# predajnik.net
KiCad netlist of a schematic drawn in EAGLE
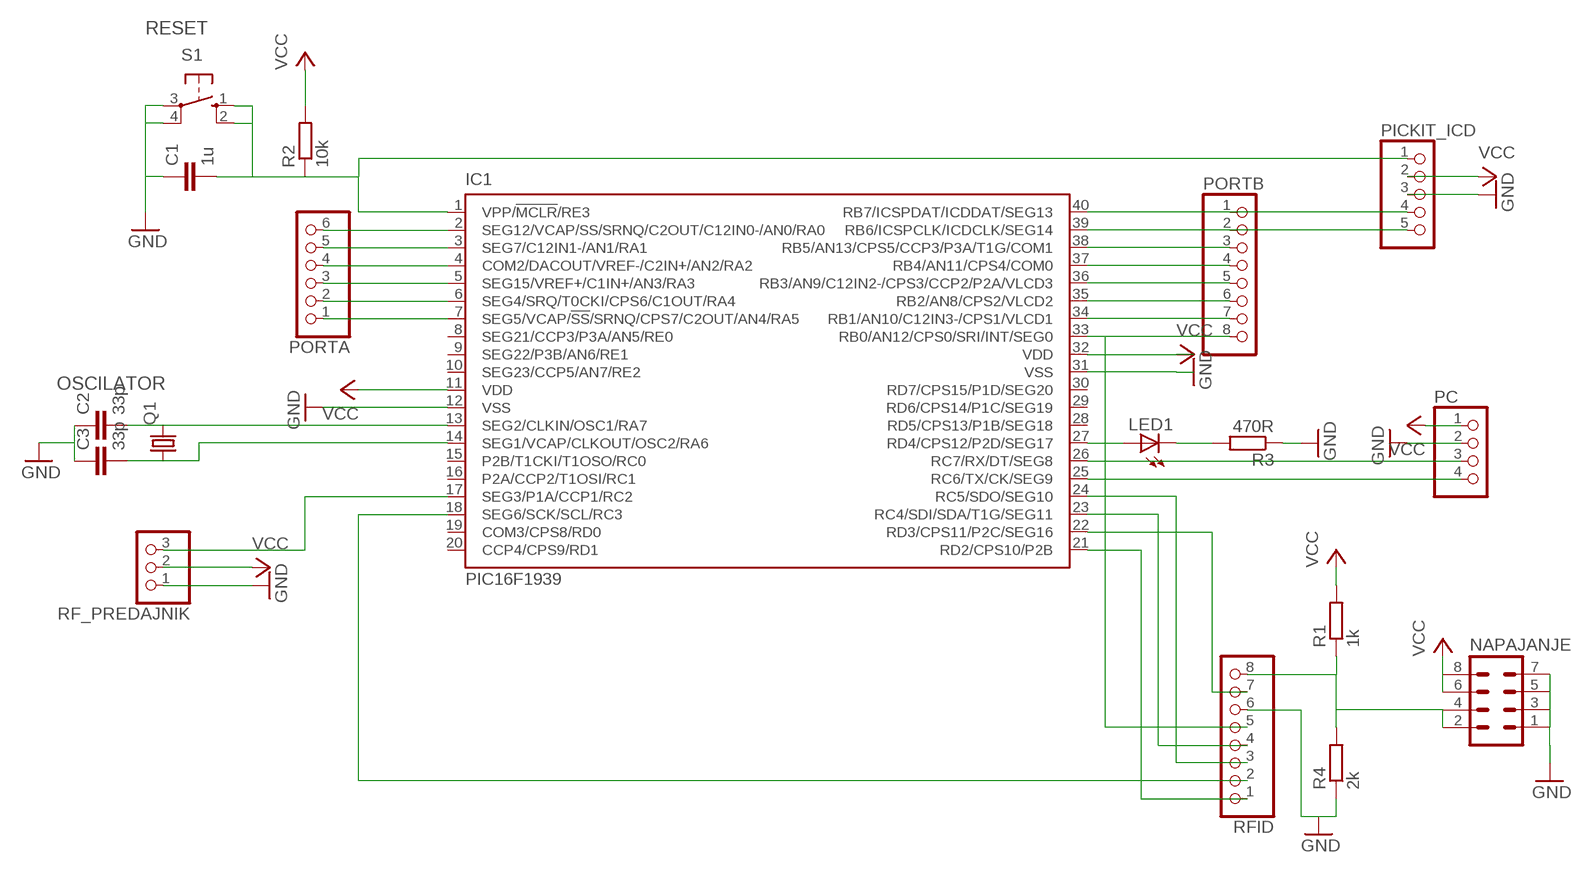
[diagram p0: schematic, sheet 1]

(export (version "E")
  (design (tool "Eeschema 10.0.6"))
  (components
    (comp (ref "C1")
      (value "1u")
      (footprint "eagle-import:C050-024X044")
      (libsource (lib "eagle-import") (part "C-EU050-024X044"))
    )
    (comp (ref "C2")
      (value "33p")
      (footprint "eagle-import:C025-024X044")
      (libsource (lib "eagle-import") (part "C-EU025-024X044"))
    )
    (comp (ref "C3")
      (value "33p")
      (footprint "eagle-import:C025-024X044")
      (libsource (lib "eagle-import") (part "C-EU025-024X044"))
    )
    (comp (ref "IC1")
      (value "PIC16F1939")
      (footprint "eagle-import:DIL40")
      (libsource (lib "eagle-import") (part "PIC16F193?"))
    )
    (comp (ref "LED1")
      (value "LED5MM")
      (footprint "eagle-import:LED5MM")
      (libsource (lib "eagle-import") (part "LED5MM"))
    )
    (comp (ref "NAPAJANJE")
      (value "MA04-2")
      (footprint "eagle-import:MA04-2")
      (libsource (lib "eagle-import") (part "MA04-2"))
    )
    (comp (ref "PC")
      (value "PINHD-1X4")
      (footprint "eagle-import:1X04")
      (libsource (lib "eagle-import") (part "PINHD-1X4"))
    )
    (comp (ref "PICKIT_ICD")
      (value "PINHD-1X5")
      (footprint "eagle-import:1X05")
      (libsource (lib "eagle-import") (part "PINHD-1X5"))
    )
    (comp (ref "PORTA")
      (value "PINHD-1X6")
      (footprint "eagle-import:1X06")
      (libsource (lib "eagle-import") (part "PINHD-1X6"))
    )
    (comp (ref "PORTB")
      (value "PINHD-1X8")
      (footprint "eagle-import:1X08")
      (libsource (lib "eagle-import") (part "PINHD-1X8"))
    )
    (comp (ref "Q1")
      (value "CRYSTALHC49S")
      (footprint "eagle-import:HC49_S")
      (libsource (lib "eagle-import") (part "CRYSTALHC49S"))
    )
    (comp (ref "R1")
      (value "1k")
      (footprint "eagle-import:0207_10")
      (libsource (lib "eagle-import") (part "R-EU_0207/10"))
    )
    (comp (ref "R2")
      (value "10k")
      (footprint "eagle-import:0207_10")
      (libsource (lib "eagle-import") (part "R-EU_0207/10"))
    )
    (comp (ref "R3")
      (value "470R")
      (footprint "eagle-import:0207_10")
      (libsource (lib "eagle-import") (part "R-EU_0207/10"))
    )
    (comp (ref "R4")
      (value "2k")
      (footprint "eagle-import:0207_10")
      (libsource (lib "eagle-import") (part "R-EU_0207/10"))
    )
    (comp (ref "RFID")
      (value "PINHD-1X8")
      (footprint "eagle-import:1X08")
      (libsource (lib "eagle-import") (part "PINHD-1X8"))
    )
    (comp (ref "RF_PREDAJNIK")
      (value "PINHD-1X3")
      (footprint "eagle-import:1X03")
      (libsource (lib "eagle-import") (part "PINHD-1X3"))
    )
    (comp (ref "S1")
      (value "10-XX")
      (footprint "eagle-import:B3F-10XX")
      (fields (field (name "MPN") "B3F-1000"))
      (libsource (lib "eagle-import") (part "10-XX"))
    )
  )
  (nets
    (net (code "1") (name "GND") (class "Default")
      (node (ref "C1") (pin "1") (pinfunction "1_1") (pintype "passive"))
      (node (ref "C2") (pin "1") (pinfunction "1_1") (pintype "passive"))
      (node (ref "C3") (pin "1") (pinfunction "1_1") (pintype "passive"))
      (node (ref "IC1") (pin "12") (pinfunction "VSS_12") (pintype "power_in"))
      (node (ref "IC1") (pin "31") (pinfunction "VSS_31") (pintype "power_in"))
      (node (ref "NAPAJANJE") (pin "1") (pinfunction "1_1") (pintype "passive"))
      (node (ref "NAPAJANJE") (pin "3") (pinfunction "3_3") (pintype "passive"))
      (node (ref "NAPAJANJE") (pin "5") (pinfunction "5_5") (pintype "passive"))
      (node (ref "NAPAJANJE") (pin "7") (pinfunction "7_7") (pintype "passive"))
      (node (ref "PC") (pin "2") (pinfunction "2_2") (pintype "passive"))
      (node (ref "PICKIT_ICD") (pin "3") (pinfunction "3_3") (pintype "passive"))
      (node (ref "R3") (pin "1") (pinfunction "1_1") (pintype "passive"))
      (node (ref "R4") (pin "1") (pinfunction "1_1") (pintype "passive"))
      (node (ref "RFID") (pin "6") (pinfunction "6_6") (pintype "passive"))
      (node (ref "RF_PREDAJNIK") (pin "1") (pinfunction "1_1") (pintype "passive"))
      (node (ref "S1") (pin "3") (pinfunction "P_3") (pintype "passive"))
      (node (ref "S1") (pin "4") (pinfunction "P1_4") (pintype "passive"))
    )
    (net (code "2") (name "Net-(IC1-COM2{slash}DACOUT{slash}VREF-{slash}C2IN+{slash}AN2{slash}RA2)") (class "Default")
      (node (ref "IC1") (pin "4") (pinfunction "COM2/DACOUT/VREF-/C2IN+/AN2/RA2_4") (pintype "bidirectional"))
      (node (ref "PORTA") (pin "4") (pinfunction "4_4") (pintype "passive"))
    )
    (net (code "3") (name "Net-(IC1-RB0{slash}AN12{slash}CPS0{slash}SRI{slash}INT{slash}SEG0)") (class "Default")
      (node (ref "IC1") (pin "33") (pinfunction "RB0/AN12/CPS0/SRI/INT/SEG0_33") (pintype "bidirectional"))
      (node (ref "PORTB") (pin "8") (pinfunction "8_8") (pintype "passive"))
      (node (ref "RFID") (pin "5") (pinfunction "5_5") (pintype "passive"))
    )
    (net (code "4") (name "Net-(IC1-RB1{slash}AN10{slash}C12IN3-{slash}CPS1{slash}VLCD1)") (class "Default")
      (node (ref "IC1") (pin "34") (pinfunction "RB1/AN10/C12IN3-/CPS1/VLCD1_34") (pintype "bidirectional"))
      (node (ref "PORTB") (pin "7") (pinfunction "7_7") (pintype "passive"))
    )
    (net (code "5") (name "Net-(IC1-RB2{slash}AN8{slash}CPS2{slash}VLCD2)") (class "Default")
      (node (ref "IC1") (pin "35") (pinfunction "RB2/AN8/CPS2/VLCD2_35") (pintype "bidirectional"))
      (node (ref "PORTB") (pin "6") (pinfunction "6_6") (pintype "passive"))
    )
    (net (code "6") (name "Net-(IC1-RB3{slash}AN9{slash}C12IN2-{slash}CPS3{slash}CCP2{slash}P2A{slash}VLCD3)") (class "Default")
      (node (ref "IC1") (pin "36") (pinfunction "RB3/AN9/C12IN2-/CPS3/CCP2/P2A/VLCD3_36") (pintype "bidirectional"))
      (node (ref "PORTB") (pin "5") (pinfunction "5_5") (pintype "passive"))
    )
    (net (code "7") (name "Net-(IC1-RB4{slash}AN11{slash}CPS4{slash}COM0)") (class "Default")
      (node (ref "IC1") (pin "37") (pinfunction "RB4/AN11/CPS4/COM0_37") (pintype "bidirectional"))
      (node (ref "PORTB") (pin "4") (pinfunction "4_4") (pintype "passive"))
    )
    (net (code "8") (name "Net-(IC1-RB5{slash}AN13{slash}CPS5{slash}CCP3{slash}P3A{slash}T1G{slash}COM1)") (class "Default")
      (node (ref "IC1") (pin "38") (pinfunction "RB5/AN13/CPS5/CCP3/P3A/T1G/COM1_38") (pintype "bidirectional"))
      (node (ref "PORTB") (pin "3") (pinfunction "3_3") (pintype "passive"))
    )
    (net (code "9") (name "Net-(IC1-RB6{slash}ICSPCLK{slash}ICDCLK{slash}SEG14)") (class "Default")
      (node (ref "IC1") (pin "39") (pinfunction "RB6/ICSPCLK/ICDCLK/SEG14_39") (pintype "bidirectional"))
      (node (ref "PICKIT_ICD") (pin "5") (pinfunction "5_5") (pintype "passive"))
      (node (ref "PORTB") (pin "2") (pinfunction "2_2") (pintype "passive"))
    )
    (net (code "10") (name "Net-(IC1-RB7{slash}ICSPDAT{slash}ICDDAT{slash}SEG13)") (class "Default")
      (node (ref "IC1") (pin "40") (pinfunction "RB7/ICSPDAT/ICDDAT/SEG13_40") (pintype "bidirectional"))
      (node (ref "PICKIT_ICD") (pin "4") (pinfunction "4_4") (pintype "passive"))
      (node (ref "PORTB") (pin "1") (pinfunction "1_1") (pintype "passive"))
    )
    (net (code "11") (name "Net-(IC1-RC4{slash}SDI{slash}SDA{slash}T1G{slash}SEG11)") (class "Default")
      (node (ref "IC1") (pin "23") (pinfunction "RC4/SDI/SDA/T1G/SEG11_23") (pintype "bidirectional"))
      (node (ref "RFID") (pin "4") (pinfunction "4_4") (pintype "passive"))
    )
    (net (code "12") (name "Net-(IC1-RC5{slash}SDO{slash}SEG10)") (class "Default")
      (node (ref "IC1") (pin "24") (pinfunction "RC5/SDO/SEG10_24") (pintype "bidirectional"))
      (node (ref "RFID") (pin "3") (pinfunction "3_3") (pintype "passive"))
    )
    (net (code "13") (name "Net-(IC1-RC6{slash}TX{slash}CK{slash}SEG9)") (class "Default")
      (node (ref "IC1") (pin "25") (pinfunction "RC6/TX/CK/SEG9_25") (pintype "bidirectional"))
      (node (ref "PC") (pin "4") (pinfunction "4_4") (pintype "passive"))
    )
    (net (code "14") (name "Net-(IC1-RC7{slash}RX{slash}DT{slash}SEG8)") (class "Default")
      (node (ref "IC1") (pin "26") (pinfunction "RC7/RX/DT/SEG8_26") (pintype "bidirectional"))
      (node (ref "PC") (pin "3") (pinfunction "3_3") (pintype "passive"))
    )
    (net (code "15") (name "Net-(IC1-RD2{slash}CPS10{slash}P2B)") (class "Default")
      (node (ref "IC1") (pin "21") (pinfunction "RD2/CPS10/P2B_21") (pintype "bidirectional"))
      (node (ref "RFID") (pin "1") (pinfunction "1_1") (pintype "passive"))
    )
    (net (code "16") (name "Net-(IC1-RD3{slash}CPS11{slash}P2C{slash}SEG16)") (class "Default")
      (node (ref "IC1") (pin "22") (pinfunction "RD3/CPS11/P2C/SEG16_22") (pintype "bidirectional"))
      (node (ref "RFID") (pin "7") (pinfunction "7_7") (pintype "passive"))
    )
    (net (code "17") (name "Net-(IC1-RD4{slash}CPS12{slash}P2D{slash}SEG17)") (class "Default")
      (node (ref "IC1") (pin "27") (pinfunction "RD4/CPS12/P2D/SEG17_27") (pintype "bidirectional"))
      (node (ref "LED1") (pin "A") (pinfunction "A_A") (pintype "passive"))
    )
    (net (code "18") (name "Net-(IC1-SEG1{slash}VCAP{slash}CLKOUT{slash}OSC2{slash}RA6)") (class "Default")
      (node (ref "C3") (pin "2") (pinfunction "2_2") (pintype "passive"))
      (node (ref "IC1") (pin "14") (pinfunction "SEG1/VCAP/CLKOUT/OSC2/RA6_14") (pintype "bidirectional"))
      (node (ref "Q1") (pin "1") (pinfunction "1_1") (pintype "passive"))
    )
    (net (code "19") (name "Net-(IC1-SEG2{slash}CLKIN{slash}OSC1{slash}RA7)") (class "Default")
      (node (ref "C2") (pin "2") (pinfunction "2_2") (pintype "passive"))
      (node (ref "IC1") (pin "13") (pinfunction "SEG2/CLKIN/OSC1/RA7_13") (pintype "bidirectional"))
      (node (ref "Q1") (pin "2") (pinfunction "2_2") (pintype "passive"))
    )
    (net (code "20") (name "Net-(IC1-SEG3{slash}P1A{slash}CCP1{slash}RC2)") (class "Default")
      (node (ref "IC1") (pin "17") (pinfunction "SEG3/P1A/CCP1/RC2_17") (pintype "bidirectional"))
      (node (ref "RF_PREDAJNIK") (pin "3") (pinfunction "3_3") (pintype "passive"))
    )
    (net (code "21") (name "Net-(IC1-SEG4{slash}SRQ{slash}T0CKI{slash}CPS6{slash}C1OUT{slash}RA4)") (class "Default")
      (node (ref "IC1") (pin "6") (pinfunction "SEG4/SRQ/T0CKI/CPS6/C1OUT/RA4_6") (pintype "bidirectional"))
      (node (ref "PORTA") (pin "2") (pinfunction "2_2") (pintype "passive"))
    )
    (net (code "22") (name "Net-(IC1-SEG5{slash}VCAP{slash}~{SS}{slash}SRNQ{slash}CPS7{slash}C2OUT{slash}AN4{slash}RA5)") (class "Default")
      (node (ref "IC1") (pin "7") (pinfunction "SEG5/VCAP/~{SS}/SRNQ/CPS7/C2OUT/AN4/RA5_7") (pintype "bidirectional"))
      (node (ref "PORTA") (pin "1") (pinfunction "1_1") (pintype "passive"))
    )
    (net (code "23") (name "Net-(IC1-SEG6{slash}SCK{slash}SCL{slash}RC3)") (class "Default")
      (node (ref "IC1") (pin "18") (pinfunction "SEG6/SCK/SCL/RC3_18") (pintype "bidirectional"))
      (node (ref "RFID") (pin "2") (pinfunction "2_2") (pintype "passive"))
    )
    (net (code "24") (name "Net-(IC1-SEG7{slash}C12IN1-{slash}AN1{slash}RA1)") (class "Default")
      (node (ref "IC1") (pin "3") (pinfunction "SEG7/C12IN1-/AN1/RA1_3") (pintype "bidirectional"))
      (node (ref "PORTA") (pin "5") (pinfunction "5_5") (pintype "passive"))
    )
    (net (code "25") (name "Net-(IC1-SEG12{slash}VCAP{slash}SS{slash}SRNQ{slash}C2OUT{slash}C12IN0-{slash}AN0{slash}RA0)") (class "Default")
      (node (ref "IC1") (pin "2") (pinfunction "SEG12/VCAP/SS/SRNQ/C2OUT/C12IN0-/AN0/RA0_2") (pintype "bidirectional"))
      (node (ref "PORTA") (pin "6") (pinfunction "6_6") (pintype "passive"))
    )
    (net (code "26") (name "Net-(IC1-SEG15{slash}VREF+{slash}C1IN+{slash}AN3{slash}RA3)") (class "Default")
      (node (ref "IC1") (pin "5") (pinfunction "SEG15/VREF+/C1IN+/AN3/RA3_5") (pintype "bidirectional"))
      (node (ref "PORTA") (pin "3") (pinfunction "3_3") (pintype "passive"))
    )
    (net (code "27") (name "Net-(IC1-VPP{slash}~{MCLR}{slash}RE3)") (class "Default")
      (node (ref "C1") (pin "2") (pinfunction "2_2") (pintype "passive"))
      (node (ref "IC1") (pin "1") (pinfunction "VPP/~{MCLR}/RE3_1") (pintype "input"))
      (node (ref "PICKIT_ICD") (pin "1") (pinfunction "1_1") (pintype "passive"))
      (node (ref "R2") (pin "1") (pinfunction "1_1") (pintype "passive"))
      (node (ref "S1") (pin "1") (pinfunction "S_1") (pintype "passive"))
      (node (ref "S1") (pin "2") (pinfunction "S1_2") (pintype "passive"))
    )
    (net (code "28") (name "Net-(LED1-C)") (class "Default")
      (node (ref "LED1") (pin "K") (pinfunction "C_K") (pintype "passive"))
      (node (ref "R3") (pin "2") (pinfunction "2_2") (pintype "passive"))
    )
    (net (code "29") (name "Net-(NAPAJANJE-Pad2)") (class "Default")
      (node (ref "NAPAJANJE") (pin "2") (pinfunction "2_2") (pintype "passive"))
      (node (ref "NAPAJANJE") (pin "4") (pinfunction "4_4") (pintype "passive"))
      (node (ref "R1") (pin "1") (pinfunction "1_1") (pintype "passive"))
      (node (ref "R4") (pin "2") (pinfunction "2_2") (pintype "passive"))
      (node (ref "RFID") (pin "8") (pinfunction "8_8") (pintype "passive"))
    )
    (net (code "30") (name "VCC") (class "Default")
      (node (ref "IC1") (pin "11") (pinfunction "VDD_11") (pintype "power_in"))
      (node (ref "IC1") (pin "32") (pinfunction "VDD_32") (pintype "power_in"))
      (node (ref "NAPAJANJE") (pin "6") (pinfunction "6_6") (pintype "passive"))
      (node (ref "NAPAJANJE") (pin "8") (pinfunction "8_8") (pintype "passive"))
      (node (ref "PC") (pin "1") (pinfunction "1_1") (pintype "passive"))
      (node (ref "PICKIT_ICD") (pin "2") (pinfunction "2_2") (pintype "passive"))
      (node (ref "R1") (pin "2") (pinfunction "2_2") (pintype "passive"))
      (node (ref "R2") (pin "2") (pinfunction "2_2") (pintype "passive"))
      (node (ref "RF_PREDAJNIK") (pin "2") (pinfunction "2_2") (pintype "passive"))
    )
    (net (code "31") (name "unconnected-(IC1-CCP4{slash}CPS9{slash}RD1-Pad20)") (class "Default")
      (node (ref "IC1") (pin "20") (pinfunction "CCP4/CPS9/RD1_20") (pintype "bidirectional"))
    )
    (net (code "32") (name "unconnected-(IC1-COM3{slash}CPS8{slash}RD0-Pad19)") (class "Default")
      (node (ref "IC1") (pin "19") (pinfunction "COM3/CPS8/RD0_19") (pintype "bidirectional"))
    )
    (net (code "33") (name "unconnected-(IC1-P2A{slash}CCP2{slash}T1OSI{slash}RC1-Pad16)") (class "Default")
      (node (ref "IC1") (pin "16") (pinfunction "P2A/CCP2/T1OSI/RC1_16") (pintype "bidirectional"))
    )
    (net (code "34") (name "unconnected-(IC1-P2B{slash}T1CKI{slash}T1OSO{slash}RC0-Pad15)") (class "Default")
      (node (ref "IC1") (pin "15") (pinfunction "P2B/T1CKI/T1OSO/RC0_15") (pintype "bidirectional"))
    )
    (net (code "35") (name "unconnected-(IC1-RD5{slash}CPS13{slash}P1B{slash}SEG18-Pad28)") (class "Default")
      (node (ref "IC1") (pin "28") (pinfunction "RD5/CPS13/P1B/SEG18_28") (pintype "bidirectional"))
    )
    (net (code "36") (name "unconnected-(IC1-RD6{slash}CPS14{slash}P1C{slash}SEG19-Pad29)") (class "Default")
      (node (ref "IC1") (pin "29") (pinfunction "RD6/CPS14/P1C/SEG19_29") (pintype "bidirectional"))
    )
    (net (code "37") (name "unconnected-(IC1-RD7{slash}CPS15{slash}P1D{slash}SEG20-Pad30)") (class "Default")
      (node (ref "IC1") (pin "30") (pinfunction "RD7/CPS15/P1D/SEG20_30") (pintype "bidirectional"))
    )
    (net (code "38") (name "unconnected-(IC1-SEG21{slash}CCP3{slash}P3A{slash}AN5{slash}RE0-Pad8)") (class "Default")
      (node (ref "IC1") (pin "8") (pinfunction "SEG21/CCP3/P3A/AN5/RE0_8") (pintype "bidirectional"))
    )
    (net (code "39") (name "unconnected-(IC1-SEG22{slash}P3B{slash}AN6{slash}RE1-Pad9)") (class "Default")
      (node (ref "IC1") (pin "9") (pinfunction "SEG22/P3B/AN6/RE1_9") (pintype "bidirectional"))
    )
    (net (code "40") (name "unconnected-(IC1-SEG23{slash}CCP5{slash}AN7{slash}RE2-Pad10)") (class "Default")
      (node (ref "IC1") (pin "10") (pinfunction "SEG23/CCP5/AN7/RE2_10") (pintype "bidirectional"))
    )
  )
)
